# VCLFO_th_2_orig.net
KiCad netlist of a schematic drawn in EAGLE
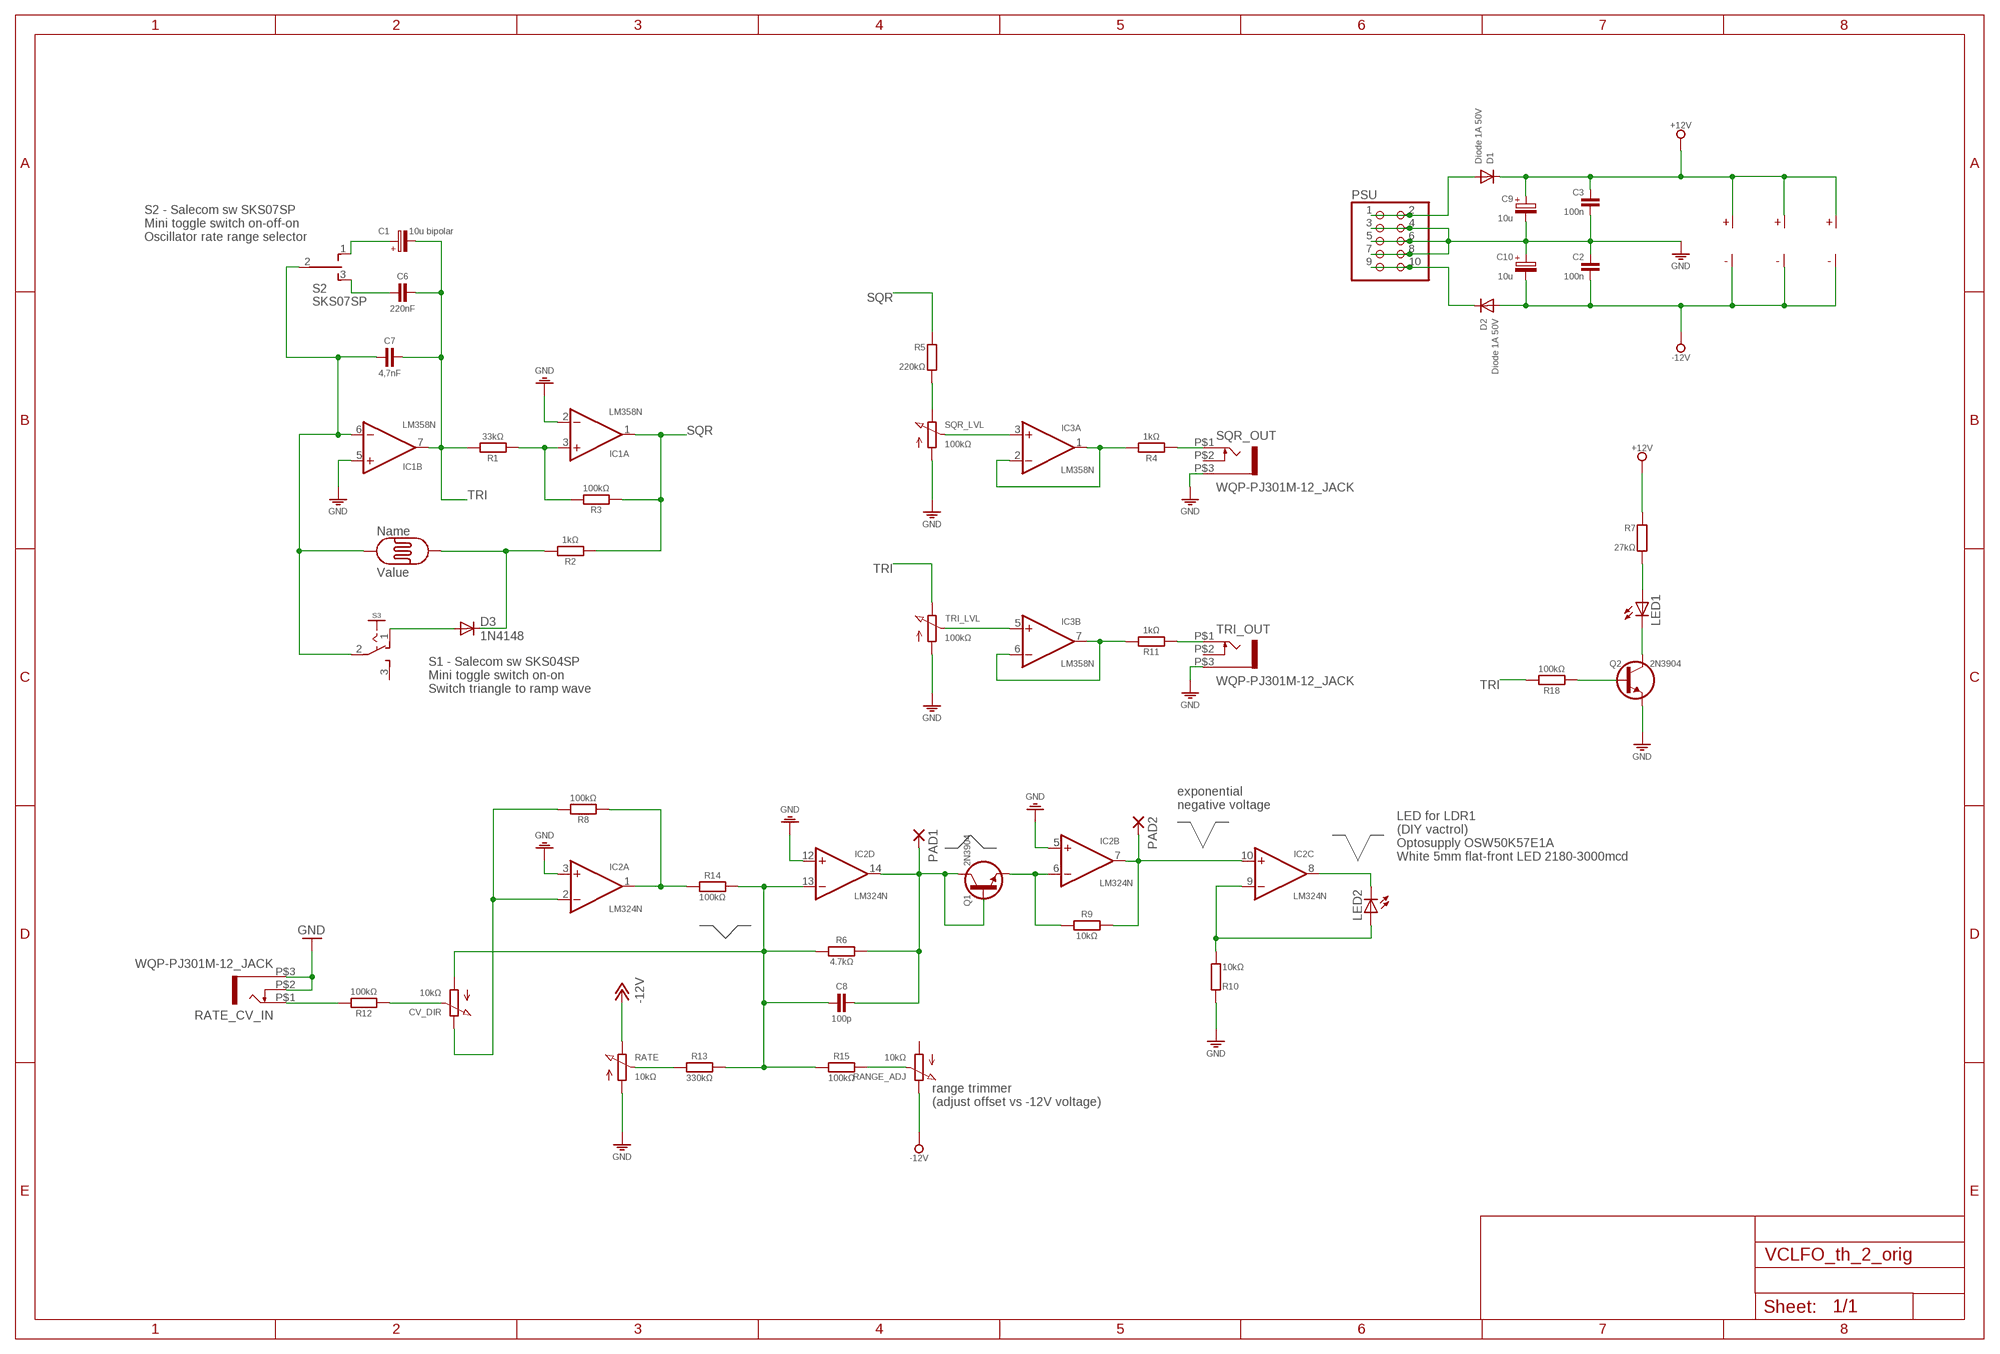
[diagram p0: schematic, sheet 1]

(export (version "E")
  (design (tool "Eeschema 10.0.6"))
  (components
    (comp (ref "C1")
      (value "10u bipolar")
      (footprint "eagle-import:E2,5-4")
      (libsource (lib "eagle-import") (part "CPOLE2,5-4"))
    )
    (comp (ref "C2")
      (value "100n")
      (footprint "eagle-import:C050-020X044_V")
      (libsource (lib "eagle-import") (part "C050-020X044/V"))
    )
    (comp (ref "C3")
      (value "100n")
      (footprint "eagle-import:C050-020X044_V")
      (libsource (lib "eagle-import") (part "C050-020X044/V"))
    )
    (comp (ref "C6")
      (value "220nF")
      (footprint "eagle-import:C050-020X044")
      (libsource (lib "eagle-import") (part "C-H050-020X044"))
    )
    (comp (ref "C7")
      (value "4,7nF")
      (footprint "eagle-import:C0750-020X044")
      (libsource (lib "eagle-import") (part "C-H075-020X044"))
    )
    (comp (ref "C8")
      (value "100p")
      (footprint "eagle-import:C025-015X024")
      (libsource (lib "eagle-import") (part "C-H025-015X024"))
    )
    (comp (ref "C9")
      (value "10u")
      (footprint "eagle-import:E2.5-4_V")
      (libsource (lib "eagle-import") (part "CPOLE2,5-4/V"))
    )
    (comp (ref "C10")
      (value "10u")
      (footprint "eagle-import:E2.5-4_V")
      (libsource (lib "eagle-import") (part "CPOLE2,5-4/V"))
    )
    (comp (ref "CV_DIR")
      (value "10kΩ")
      (footprint "eagle-import:CONN-3P")
      (libsource (lib "eagle-import") (part "POT-3P"))
    )
    (comp (ref "D1")
      (value "Diode 1A 50V")
      (footprint "eagle-import:DO35-2_54")
      (libsource (lib "eagle-import") (part "1N4002-2.54"))
    )
    (comp (ref "D2")
      (value "Diode 1A 50V")
      (footprint "eagle-import:DO35-2_54A")
      (libsource (lib "eagle-import") (part "1N4002-2.54A"))
    )
    (comp (ref "D3")
      (value "1N4148")
      (footprint "eagle-import:D-5")
      (libsource (lib "eagle-import") (part "DIODE-D-5"))
    )
    (comp (ref "IC1")
      (value "LM358N")
      (footprint "eagle-import:DIL08")
      (libsource (lib "eagle-import") (part "LM358N"))
    )
    (comp (ref "IC2")
      (value "LM324N")
      (footprint "eagle-import:DIL14")
      (libsource (lib "eagle-import") (part "LM324N"))
    )
    (comp (ref "IC3")
      (value "LM358N")
      (footprint "eagle-import:DIL08")
      (libsource (lib "eagle-import") (part "LM358N"))
    )
    (comp (ref "LED1")
      (value "LED5MM")
      (footprint "eagle-import:LED5MM")
      (libsource (lib "eagle-import") (part "LED5MM"))
    )
    (comp (ref "LED2")
      (value "LED5MM")
      (footprint "eagle-import:LED5MM")
      (libsource (lib "eagle-import") (part "LED5MM"))
    )
    (comp (ref "PAD1")
      (value "1,6/0,8")
      (footprint "eagle-import:1,6_0,8")
      (libsource (lib "eagle-import") (part "1,6/0,8"))
    )
    (comp (ref "PAD2")
      (value "1,6/0,8")
      (footprint "eagle-import:1,6_0,8")
      (libsource (lib "eagle-import") (part "1,6/0,8"))
    )
    (comp (ref "PSU")
      (value "PINHD-2X5")
      (footprint "eagle-import:2X05")
      (libsource (lib "eagle-import") (part "PINHD-2X5"))
    )
    (comp (ref "Q1")
      (value "2N3904")
      (footprint "eagle-import:TO92")
      (libsource (lib "eagle-import") (part "2N3904"))
    )
    (comp (ref "Q2")
      (value "2N3904")
      (footprint "eagle-import:TO92")
      (libsource (lib "eagle-import") (part "2N3904"))
    )
    (comp (ref "R1")
      (value "33kΩ")
      (footprint "eagle-import:0204_10")
      (libsource (lib "eagle-import") (part "R-H0204/10"))
    )
    (comp (ref "R2")
      (value "1kΩ")
      (footprint "eagle-import:0204_10")
      (libsource (lib "eagle-import") (part "R-H0204/10"))
    )
    (comp (ref "R3")
      (value "100kΩ")
      (footprint "eagle-import:0204_10")
      (libsource (lib "eagle-import") (part "R-H0204/10"))
    )
    (comp (ref "R4")
      (value "1kΩ")
      (footprint "eagle-import:0204_10")
      (libsource (lib "eagle-import") (part "R-H0204/10"))
    )
    (comp (ref "R5")
      (value "220kΩ")
      (footprint "eagle-import:0204_10-V")
      (libsource (lib "eagle-import") (part "R0204/10-V"))
    )
    (comp (ref "R6")
      (value "4.7kΩ")
      (footprint "eagle-import:0204_10")
      (libsource (lib "eagle-import") (part "R-H0204/10"))
    )
    (comp (ref "R7")
      (value "27kΩ")
      (footprint "eagle-import:0204_10-V")
      (libsource (lib "eagle-import") (part "R0204/10-V"))
    )
    (comp (ref "R8")
      (value "100kΩ")
      (footprint "eagle-import:0204_10")
      (libsource (lib "eagle-import") (part "R-H0204/10"))
    )
    (comp (ref "R9")
      (value "10kΩ")
      (footprint "eagle-import:0204_10")
      (libsource (lib "eagle-import") (part "R-H0204/10"))
    )
    (comp (ref "R10")
      (value "10kΩ")
      (footprint "eagle-import:0204_10")
      (libsource (lib "eagle-import") (part "R0204/10"))
    )
    (comp (ref "R11")
      (value "1kΩ")
      (footprint "eagle-import:0204_10")
      (libsource (lib "eagle-import") (part "R-H0204/10"))
    )
    (comp (ref "R12")
      (value "100kΩ")
      (footprint "eagle-import:0204_10")
      (libsource (lib "eagle-import") (part "R-H0204/10"))
    )
    (comp (ref "R13")
      (value "330kΩ")
      (footprint "eagle-import:0204_10")
      (libsource (lib "eagle-import") (part "R-H0204/10"))
    )
    (comp (ref "R14")
      (value "100kΩ")
      (footprint "eagle-import:0204_10")
      (libsource (lib "eagle-import") (part "R-H0204/10"))
    )
    (comp (ref "R15")
      (value "100kΩ")
      (footprint "eagle-import:0204_10")
      (libsource (lib "eagle-import") (part "R-H0204/10"))
    )
    (comp (ref "R17")
      (value "Token PGM5539")
      (footprint "eagle-import:PHOTOCELL")
      (libsource (lib "eagle-import") (part "PHOTOCELLPTH"))
    )
    (comp (ref "R18")
      (value "100kΩ")
      (footprint "eagle-import:0204_10")
      (libsource (lib "eagle-import") (part "R-H0204/10"))
    )
    (comp (ref "RANGE_ADJ")
      (value "10kΩ")
      (footprint "eagle-import:CONN-3P")
      (libsource (lib "eagle-import") (part "POT-3P"))
    )
    (comp (ref "RATE")
      (value "10kΩ")
      (footprint "eagle-import:CONN-3P")
      (libsource (lib "eagle-import") (part "POT-3P"))
    )
    (comp (ref "RATE_CV_IN")
      (value "WQP-PJ301M-12_JACK")
      (footprint "eagle-import:WQP-PJ301M-12_JACK")
      (libsource (lib "eagle-import") (part "WQP-PJ301M-12_JACK"))
    )
    (comp (ref "S2")
      (value "SKS07SP")
      (footprint "eagle-import:SLSW-1P2T-H")
      (libsource (lib "eagle-import") (part "SL-SW-ON-OFF-ON-H"))
    )
    (comp (ref "S3")
      (value "SKS04SP")
      (footprint "eagle-import:SLSW-1P2T-H")
      (libsource (lib "eagle-import") (part "SL-SW-1P-2T-H"))
    )
    (comp (ref "SQR_LVL")
      (value "100kΩ")
      (footprint "eagle-import:CONN-3P")
      (libsource (lib "eagle-import") (part "POT-3P"))
    )
    (comp (ref "SQR_OUT")
      (value "WQP-PJ301M-12_JACK")
      (footprint "eagle-import:WQP-PJ301M-12_JACK")
      (libsource (lib "eagle-import") (part "WQP-PJ301M-12_JACK"))
    )
    (comp (ref "TRI_LVL")
      (value "100kΩ")
      (footprint "eagle-import:CONN-3P")
      (libsource (lib "eagle-import") (part "POT-3P"))
    )
    (comp (ref "TRI_OUT")
      (value "WQP-PJ301M-12_JACK")
      (footprint "eagle-import:WQP-PJ301M-12_JACK")
      (libsource (lib "eagle-import") (part "WQP-PJ301M-12_JACK"))
    )
  )
  (nets
    (net (code "1") (name "+12V") (class "Default")
      (node (ref "C3") (pin "1") (pinfunction "1_1") (pintype "passive"))
      (node (ref "C9") (pin "+") (pinfunction "+_+") (pintype "passive"))
      (node (ref "D1") (pin "C") (pinfunction "C_C") (pintype "passive"))
      (node (ref "IC1") (pin "8") (pinfunction "V+_8") (pintype "power_in"))
      (node (ref "IC2") (pin "4") (pinfunction "V+_4") (pintype "power_in"))
      (node (ref "IC3") (pin "8") (pinfunction "V+_8") (pintype "power_in"))
      (node (ref "R7") (pin "1") (pinfunction "1_1") (pintype "passive"))
    )
    (net (code "2") (name "-12V") (class "Default")
      (node (ref "C10") (pin "-") (pinfunction "-_-") (pintype "passive"))
      (node (ref "C2") (pin "2") (pinfunction "2_2") (pintype "passive"))
      (node (ref "D2") (pin "A") (pinfunction "A_A") (pintype "passive"))
      (node (ref "IC1") (pin "4") (pinfunction "V-_4") (pintype "power_in"))
      (node (ref "IC2") (pin "11") (pinfunction "V-_11") (pintype "power_in"))
      (node (ref "IC3") (pin "4") (pinfunction "V-_4") (pintype "power_in"))
      (node (ref "RANGE_ADJ") (pin "3") (pinfunction "E_3") (pintype "passive"))
      (node (ref "RATE") (pin "3") (pinfunction "E_3") (pintype "passive"))
    )
    (net (code "3") (name "/SQR") (class "Default")
      (node (ref "IC1") (pin "1") (pinfunction "OUT_1") (pintype "output"))
      (node (ref "R2") (pin "1") (pinfunction "1_1") (pintype "passive"))
      (node (ref "R3") (pin "1") (pinfunction "1_1") (pintype "passive"))
      (node (ref "R5") (pin "1") (pinfunction "1_1") (pintype "passive"))
    )
    (net (code "4") (name "/TRI") (class "Default")
      (node (ref "C1") (pin "-") (pinfunction "-_-") (pintype "passive"))
      (node (ref "C6") (pin "2") (pinfunction "2_2") (pintype "passive"))
      (node (ref "C7") (pin "2") (pinfunction "2_2") (pintype "passive"))
      (node (ref "IC1") (pin "7") (pinfunction "OUT_7") (pintype "output"))
      (node (ref "R1") (pin "2") (pinfunction "2_2") (pintype "passive"))
      (node (ref "R18") (pin "2") (pinfunction "2_2") (pintype "passive"))
      (node (ref "TRI_LVL") (pin "3") (pinfunction "E_3") (pintype "passive"))
    )
    (net (code "5") (name "GND") (class "Default")
      (node (ref "C10") (pin "+") (pinfunction "+_+") (pintype "passive"))
      (node (ref "C2") (pin "1") (pinfunction "1_1") (pintype "passive"))
      (node (ref "C3") (pin "2") (pinfunction "2_2") (pintype "passive"))
      (node (ref "C9") (pin "-") (pinfunction "-_-") (pintype "passive"))
      (node (ref "IC1") (pin "2") (pinfunction "-IN_2") (pintype "input"))
      (node (ref "IC1") (pin "5") (pinfunction "+IN_5") (pintype "input"))
      (node (ref "IC2") (pin "12") (pinfunction "+IN_12") (pintype "input"))
      (node (ref "IC2") (pin "3") (pinfunction "+IN_3") (pintype "input"))
      (node (ref "IC2") (pin "5") (pinfunction "+IN_5") (pintype "input"))
      (node (ref "PSU") (pin "3") (pinfunction "3_3") (pintype "passive"))
      (node (ref "PSU") (pin "4") (pinfunction "4_4") (pintype "passive"))
      (node (ref "PSU") (pin "5") (pinfunction "5_5") (pintype "passive"))
      (node (ref "PSU") (pin "6") (pinfunction "6_6") (pintype "passive"))
      (node (ref "PSU") (pin "7") (pinfunction "7_7") (pintype "passive"))
      (node (ref "PSU") (pin "8") (pinfunction "8_8") (pintype "passive"))
      (node (ref "Q2") (pin "1") (pinfunction "E_1") (pintype "passive"))
      (node (ref "R10") (pin "2") (pinfunction "1_2") (pintype "passive"))
      (node (ref "RATE") (pin "1") (pinfunction "A_1") (pintype "passive"))
      (node (ref "RATE_CV_IN") (pin "P$2") (pinfunction "3_P$2") (pintype "passive"))
      (node (ref "RATE_CV_IN") (pin "P$3") (pinfunction "1_P$3") (pintype "passive"))
      (node (ref "SQR_LVL") (pin "1") (pinfunction "A_1") (pintype "passive"))
      (node (ref "SQR_OUT") (pin "P$3") (pinfunction "1_P$3") (pintype "passive"))
      (node (ref "TRI_LVL") (pin "1") (pinfunction "A_1") (pintype "passive"))
      (node (ref "TRI_OUT") (pin "P$3") (pinfunction "1_P$3") (pintype "passive"))
    )
    (net (code "6") (name "Net-(CV_DIR-A)") (class "Default")
      (node (ref "C8") (pin "1") (pinfunction "1_1") (pintype "passive"))
      (node (ref "CV_DIR") (pin "1") (pinfunction "A_1") (pintype "passive"))
      (node (ref "IC2") (pin "13") (pinfunction "-IN_13") (pintype "input"))
      (node (ref "R13") (pin "2") (pinfunction "2_2") (pintype "passive"))
      (node (ref "R14") (pin "2") (pinfunction "2_2") (pintype "passive"))
      (node (ref "R15") (pin "1") (pinfunction "1_1") (pintype "passive"))
      (node (ref "R6") (pin "1") (pinfunction "1_1") (pintype "passive"))
    )
    (net (code "7") (name "Net-(CV_DIR-E)") (class "Default")
      (node (ref "CV_DIR") (pin "3") (pinfunction "E_3") (pintype "passive"))
      (node (ref "IC2") (pin "2") (pinfunction "-IN_2") (pintype "input"))
      (node (ref "R8") (pin "2") (pinfunction "2_2") (pintype "passive"))
    )
    (net (code "8") (name "Net-(CV_DIR-S)") (class "Default")
      (node (ref "CV_DIR") (pin "2") (pinfunction "S_2") (pintype "passive"))
      (node (ref "R12") (pin "1") (pinfunction "1_1") (pintype "passive"))
    )
    (net (code "9") (name "Net-(D1-PadA)") (class "Default")
      (node (ref "D1") (pin "A") (pinfunction "A_A") (pintype "passive"))
      (node (ref "PSU") (pin "1") (pinfunction "1_1") (pintype "passive"))
      (node (ref "PSU") (pin "2") (pinfunction "2_2") (pintype "passive"))
    )
    (net (code "10") (name "Net-(D2-PadC)") (class "Default")
      (node (ref "D2") (pin "C") (pinfunction "C_C") (pintype "passive"))
      (node (ref "PSU") (pin "10") (pinfunction "10_10") (pintype "passive"))
      (node (ref "PSU") (pin "9") (pinfunction "9_9") (pintype "passive"))
    )
    (net (code "11") (name "Net-(IC1A-+IN)") (class "Default")
      (node (ref "IC1") (pin "3") (pinfunction "+IN_3") (pintype "input"))
      (node (ref "R1") (pin "1") (pinfunction "1_1") (pintype "passive"))
      (node (ref "R3") (pin "2") (pinfunction "2_2") (pintype "passive"))
    )
    (net (code "12") (name "Net-(IC1B--IN)") (class "Default")
      (node (ref "C7") (pin "1") (pinfunction "1_1") (pintype "passive"))
      (node (ref "IC1") (pin "6") (pinfunction "-IN_6") (pintype "input"))
      (node (ref "R17") (pin "1") (pinfunction "P$1_1") (pintype "bidirectional"))
      (node (ref "S2") (pin "2") (pinfunction "P_2") (pintype "passive"))
      (node (ref "S3") (pin "2") (pinfunction "P_2") (pintype "passive"))
    )
    (net (code "13") (name "Net-(IC2A-OUT)") (class "Default")
      (node (ref "IC2") (pin "1") (pinfunction "OUT_1") (pintype "output"))
      (node (ref "R14") (pin "1") (pinfunction "1_1") (pintype "passive"))
      (node (ref "R8") (pin "1") (pinfunction "1_1") (pintype "passive"))
    )
    (net (code "14") (name "Net-(IC2B--IN)") (class "Default")
      (node (ref "IC2") (pin "6") (pinfunction "-IN_6") (pintype "input"))
      (node (ref "Q1") (pin "1") (pinfunction "E_1") (pintype "passive"))
      (node (ref "R9") (pin "1") (pinfunction "1_1") (pintype "passive"))
    )
    (net (code "15") (name "Net-(IC2B-OUT)") (class "Default")
      (node (ref "IC2") (pin "10") (pinfunction "+IN_10") (pintype "input"))
      (node (ref "IC2") (pin "7") (pinfunction "OUT_7") (pintype "output"))
      (node (ref "PAD2") (pin "1") (pinfunction "P_1") (pintype "passive"))
      (node (ref "R9") (pin "2") (pinfunction "2_2") (pintype "passive"))
    )
    (net (code "16") (name "Net-(IC2C--IN)") (class "Default")
      (node (ref "IC2") (pin "9") (pinfunction "-IN_9") (pintype "input"))
      (node (ref "LED2") (pin "A") (pinfunction "A_A") (pintype "passive"))
      (node (ref "R10") (pin "1") (pinfunction "2_1") (pintype "passive"))
    )
    (net (code "17") (name "Net-(IC2C-OUT)") (class "Default")
      (node (ref "IC2") (pin "8") (pinfunction "OUT_8") (pintype "output"))
      (node (ref "LED2") (pin "K") (pinfunction "C_K") (pintype "passive"))
    )
    (net (code "18") (name "Net-(IC2D-OUT)") (class "Default")
      (node (ref "C8") (pin "2") (pinfunction "2_2") (pintype "passive"))
      (node (ref "IC2") (pin "14") (pinfunction "OUT_14") (pintype "output"))
      (node (ref "PAD1") (pin "1") (pinfunction "P_1") (pintype "passive"))
      (node (ref "Q1") (pin "2") (pinfunction "B_2") (pintype "passive"))
      (node (ref "Q1") (pin "3") (pinfunction "C_3") (pintype "passive"))
      (node (ref "R6") (pin "2") (pinfunction "2_2") (pintype "passive"))
    )
    (net (code "19") (name "Net-(IC3A-+IN)") (class "Default")
      (node (ref "IC3") (pin "3") (pinfunction "+IN_3") (pintype "input"))
      (node (ref "SQR_LVL") (pin "2") (pinfunction "S_2") (pintype "passive"))
    )
    (net (code "20") (name "Net-(IC3A--IN)") (class "Default")
      (node (ref "IC3") (pin "1") (pinfunction "OUT_1") (pintype "output"))
      (node (ref "IC3") (pin "2") (pinfunction "-IN_2") (pintype "input"))
      (node (ref "R4") (pin "2") (pinfunction "2_2") (pintype "passive"))
    )
    (net (code "21") (name "Net-(IC3B-+IN)") (class "Default")
      (node (ref "IC3") (pin "5") (pinfunction "+IN_5") (pintype "input"))
      (node (ref "TRI_LVL") (pin "2") (pinfunction "S_2") (pintype "passive"))
    )
    (net (code "22") (name "Net-(IC3B--IN)") (class "Default")
      (node (ref "IC3") (pin "6") (pinfunction "-IN_6") (pintype "input"))
      (node (ref "IC3") (pin "7") (pinfunction "OUT_7") (pintype "output"))
      (node (ref "R11") (pin "2") (pinfunction "2_2") (pintype "passive"))
    )
    (net (code "23") (name "Net-(LED1-C)") (class "Default")
      (node (ref "LED1") (pin "K") (pinfunction "C_K") (pintype "passive"))
      (node (ref "Q2") (pin "3") (pinfunction "C_3") (pintype "passive"))
    )
    (net (code "24") (name "Net-(LED1-PadA)") (class "Default")
      (node (ref "LED1") (pin "A") (pinfunction "A_A") (pintype "passive"))
      (node (ref "R7") (pin "2") (pinfunction "2_2") (pintype "passive"))
    )
    (net (code "25") (name "Net-(Q2-B)") (class "Default")
      (node (ref "Q2") (pin "2") (pinfunction "B_2") (pintype "passive"))
      (node (ref "R18") (pin "1") (pinfunction "1_1") (pintype "passive"))
    )
    (net (code "26") (name "Net-(R17-P$2)") (class "Default")
      (node (ref "D3") (pin "C") (pinfunction "C_C") (pintype "passive"))
      (node (ref "R17") (pin "2") (pinfunction "P$2_2") (pintype "bidirectional"))
      (node (ref "R2") (pin "2") (pinfunction "2_2") (pintype "passive"))
    )
    (net (code "27") (name "Net-(RANGE_ADJ-S)") (class "Default")
      (node (ref "R15") (pin "2") (pinfunction "2_2") (pintype "passive"))
      (node (ref "RANGE_ADJ") (pin "2") (pinfunction "S_2") (pintype "passive"))
    )
    (net (code "28") (name "Net-(RATE-S)") (class "Default")
      (node (ref "R13") (pin "1") (pinfunction "1_1") (pintype "passive"))
      (node (ref "RATE") (pin "2") (pinfunction "S_2") (pintype "passive"))
    )
    (net (code "29") (name "Net-(RATE_CV_IN-2)") (class "Default")
      (node (ref "R12") (pin "2") (pinfunction "2_2") (pintype "passive"))
      (node (ref "RATE_CV_IN") (pin "P$1") (pinfunction "2_P$1") (pintype "passive"))
    )
    (net (code "30") (name "Net-(S2-O)") (class "Default")
      (node (ref "C1") (pin "+") (pinfunction "+_+") (pintype "passive"))
      (node (ref "S2") (pin "1") (pinfunction "O_1") (pintype "passive"))
    )
    (net (code "31") (name "Net-(S2-S)") (class "Default")
      (node (ref "C6") (pin "1") (pinfunction "1_1") (pintype "passive"))
      (node (ref "S2") (pin "3") (pinfunction "S_3") (pintype "passive"))
    )
    (net (code "32") (name "Net-(S3-O)") (class "Default")
      (node (ref "D3") (pin "A") (pinfunction "A_A") (pintype "passive"))
      (node (ref "S3") (pin "1") (pinfunction "O_1") (pintype "passive"))
    )
    (net (code "33") (name "Net-(SQR_LVL-E)") (class "Default")
      (node (ref "R5") (pin "2") (pinfunction "2_2") (pintype "passive"))
      (node (ref "SQR_LVL") (pin "3") (pinfunction "E_3") (pintype "passive"))
    )
    (net (code "34") (name "Net-(SQR_OUT-2)") (class "Default")
      (node (ref "R4") (pin "1") (pinfunction "1_1") (pintype "passive"))
      (node (ref "SQR_OUT") (pin "P$1") (pinfunction "2_P$1") (pintype "passive"))
    )
    (net (code "35") (name "Net-(TRI_OUT-2)") (class "Default")
      (node (ref "R11") (pin "1") (pinfunction "1_1") (pintype "passive"))
      (node (ref "TRI_OUT") (pin "P$1") (pinfunction "2_P$1") (pintype "passive"))
    )
    (net (code "36") (name "unconnected-(RANGE_ADJ-A-Pad1)") (class "Default")
      (node (ref "RANGE_ADJ") (pin "1") (pinfunction "A_1") (pintype "passive"))
    )
    (net (code "37") (name "unconnected-(S3-S-Pad3)") (class "Default")
      (node (ref "S3") (pin "3") (pinfunction "S_3") (pintype "passive"))
    )
    (net (code "38") (name "unconnected-(SQR_OUT-3-PadP$2)") (class "Default")
      (node (ref "SQR_OUT") (pin "P$2") (pinfunction "3_P$2") (pintype "passive"))
    )
    (net (code "39") (name "unconnected-(TRI_OUT-3-PadP$2)") (class "Default")
      (node (ref "TRI_OUT") (pin "P$2") (pinfunction "3_P$2") (pintype "passive"))
    )
  )
)
